# Serial.net
KiCad netlist of a schematic drawn in Altium Designer
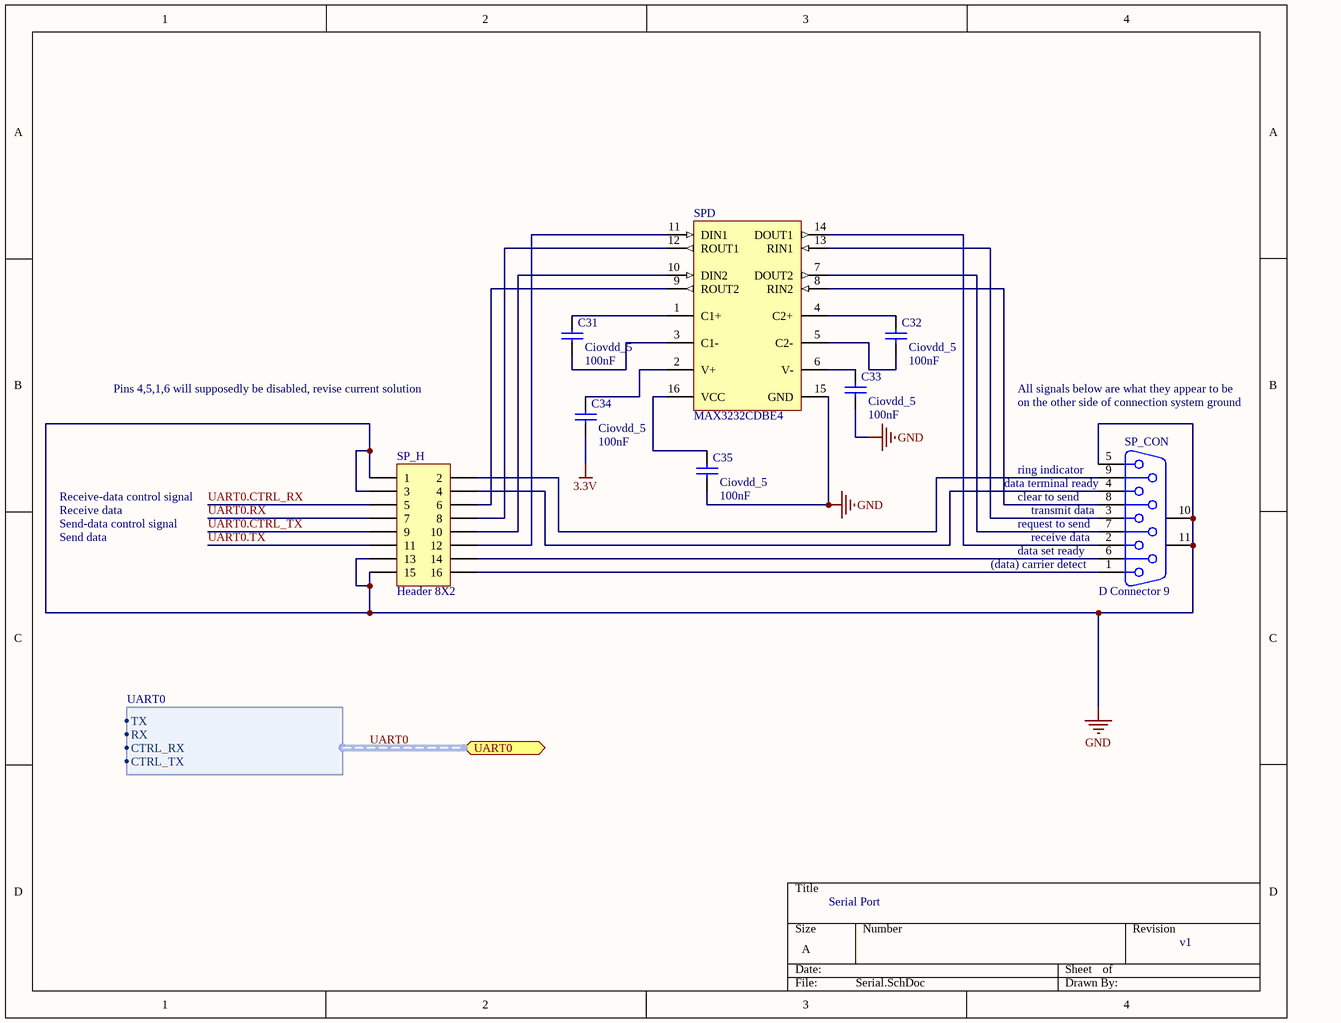
[diagram p0: Serial.SchDoc]

(export (version "E")
  (design (tool "Eeschema 10.0.6"))
  (components
    (comp (ref "C31")
      (value "Ciovdd_5")
      (footprint "C1206")
      (description "Capacitor (Semiconductor SIM Model)")
      (fields
        (field (name "ALTIUM_VALUE") "100nF")
        (field (name "MANUFACTURER") "AVX")
        (field (name "MANUFACTURER PART NUMBER") "02016D104KAT2A")
        (field (name "PUBLISHER") "Altium Limited")
      )
      (libsource (lib "Miscellaneous Devices") (part "Cap Semi"))
    )
    (comp (ref "C32")
      (value "Ciovdd_5")
      (footprint "C1206")
      (description "Capacitor (Semiconductor SIM Model)")
      (fields
        (field (name "ALTIUM_VALUE") "100nF")
        (field (name "MANUFACTURER") "AVX")
        (field (name "MANUFACTURER PART NUMBER") "02016D104KAT2A")
        (field (name "PUBLISHER") "Altium Limited")
      )
      (libsource (lib "Miscellaneous Devices") (part "Cap Semi"))
    )
    (comp (ref "C33")
      (value "Ciovdd_5")
      (footprint "C1206")
      (description "Capacitor (Semiconductor SIM Model)")
      (fields
        (field (name "ALTIUM_VALUE") "100nF")
        (field (name "MANUFACTURER") "AVX")
        (field (name "MANUFACTURER PART NUMBER") "02016D104KAT2A")
        (field (name "PUBLISHER") "Altium Limited")
      )
      (libsource (lib "Miscellaneous Devices") (part "Cap Semi"))
    )
    (comp (ref "C34")
      (value "Ciovdd_5")
      (footprint "C1206")
      (description "Capacitor (Semiconductor SIM Model)")
      (fields
        (field (name "ALTIUM_VALUE") "100nF")
        (field (name "MANUFACTURER") "AVX")
        (field (name "MANUFACTURER PART NUMBER") "02016D104KAT2A")
        (field (name "PUBLISHER") "Altium Limited")
      )
      (libsource (lib "Miscellaneous Devices") (part "Cap Semi"))
    )
    (comp (ref "C35")
      (value "Ciovdd_5")
      (footprint "C1206")
      (description "Capacitor (Semiconductor SIM Model)")
      (fields
        (field (name "ALTIUM_VALUE") "100nF")
        (field (name "MANUFACTURER") "AVX")
        (field (name "MANUFACTURER PART NUMBER") "02016D104KAT2A")
        (field (name "PUBLISHER") "Altium Limited")
      )
      (libsource (lib "Miscellaneous Devices") (part "Cap Semi"))
    )
    (comp (ref "SPD")
      (value "MAX3232CDBE4")
      (footprint "TI-DB16_L")
      (libsource (lib "Altium Content Vault") (part "TI-MAX3232-SSOP_DB-16"))
    )
    (comp (ref "SP_CON")
      (value "D Connector 9")
      (footprint "DSUB1.385-2H9")
      (description "Receptacle Assembly, 9 Position, Right Angle")
      (fields (field (name "PUBLISHER") "Altium Limited"))
      (libsource (lib "Miscellaneous Connectors") (part "D Connector 9"))
    )
    (comp (ref "SP_H")
      (value "Header 8X2")
      (footprint "HDR2X8")
      (description "Header, 8-Pin, Dual row")
      (fields (field (name "PUBLISHER") "Altium Limited"))
      (libsource (lib "Miscellaneous Connectors") (part "Header 8X2"))
    )
  )
  (nets
    (net (code "2") (name "/UART0.CTRL_RX") (class "Default")
      (node (ref "SP_H") (pin "5") (pinfunction "5_5") (pintype "passive"))
    )
    (net (code "3") (name "/UART0.CTRL_TX") (class "Default")
      (node (ref "SP_H") (pin "9") (pinfunction "9_9") (pintype "passive"))
    )
    (net (code "4") (name "/UART0.RX") (class "Default")
      (node (ref "SP_H") (pin "7") (pinfunction "7_7") (pintype "passive"))
    )
    (net (code "5") (name "/UART0.TX") (class "Default")
      (node (ref "SP_H") (pin "11") (pinfunction "11_11") (pintype "passive"))
    )
    (net (code "7") (name "3.3V") (class "Default")
      (node (ref "C34") (pin "1") (pinfunction "1_1") (pintype "passive"))
    )
    (net (code "8") (name "GND") (class "Default")
      (node (ref "C33") (pin "1") (pinfunction "1_1") (pintype "passive"))
      (node (ref "C35") (pin "1") (pinfunction "1_1") (pintype "passive"))
      (node (ref "SPD") (pin "15") (pinfunction "GND_15") (pintype "power_in"))
      (node (ref "SP_CON") (pin "10") (pinfunction "MH1_10") (pintype "passive"))
      (node (ref "SP_CON") (pin "11") (pinfunction "MH2_11") (pintype "passive"))
      (node (ref "SP_CON") (pin "5") (pinfunction "5_5") (pintype "passive"))
      (node (ref "SP_H") (pin "1") (pinfunction "1_1") (pintype "passive"))
      (node (ref "SP_H") (pin "13") (pinfunction "13_13") (pintype "passive"))
      (node (ref "SP_H") (pin "15") (pinfunction "15_15") (pintype "passive"))
      (node (ref "SP_H") (pin "3") (pinfunction "3_3") (pintype "passive"))
    )
    (net (code "9") (name "Net-(SPD-C1+)") (class "Default")
      (node (ref "C31") (pin "2") (pinfunction "2_2") (pintype "passive"))
      (node (ref "SPD") (pin "1") (pinfunction "C1+_1") (pintype "passive"))
    )
    (net (code "10") (name "Net-(SPD-C1-)") (class "Default")
      (node (ref "C31") (pin "1") (pinfunction "1_1") (pintype "passive"))
      (node (ref "SPD") (pin "3") (pinfunction "C1-_3") (pintype "passive"))
    )
    (net (code "11") (name "Net-(SPD-C2+)") (class "Default")
      (node (ref "C32") (pin "2") (pinfunction "2_2") (pintype "passive"))
      (node (ref "SPD") (pin "4") (pinfunction "C2+_4") (pintype "passive"))
    )
    (net (code "12") (name "Net-(SPD-C2-)") (class "Default")
      (node (ref "C32") (pin "1") (pinfunction "1_1") (pintype "passive"))
      (node (ref "SPD") (pin "5") (pinfunction "C2-_5") (pintype "passive"))
    )
    (net (code "13") (name "Net-(SPD-DIN1)") (class "Default")
      (node (ref "SPD") (pin "11") (pinfunction "DIN1_11") (pintype "input"))
      (node (ref "SP_H") (pin "12") (pinfunction "12_12") (pintype "passive"))
    )
    (net (code "14") (name "Net-(SPD-DIN2)") (class "Default")
      (node (ref "SPD") (pin "10") (pinfunction "DIN2_10") (pintype "input"))
      (node (ref "SP_H") (pin "10") (pinfunction "10_10") (pintype "passive"))
    )
    (net (code "15") (name "Net-(SPD-DOUT1)") (class "Default")
      (node (ref "SPD") (pin "14") (pinfunction "DOUT1_14") (pintype "output"))
      (node (ref "SP_CON") (pin "2") (pinfunction "2_2") (pintype "passive"))
    )
    (net (code "16") (name "Net-(SPD-DOUT2)") (class "Default")
      (node (ref "SPD") (pin "7") (pinfunction "DOUT2_7") (pintype "output"))
      (node (ref "SP_CON") (pin "7") (pinfunction "7_7") (pintype "passive"))
    )
    (net (code "17") (name "Net-(SPD-RIN1)") (class "Default")
      (node (ref "SPD") (pin "13") (pinfunction "RIN1_13") (pintype "input"))
      (node (ref "SP_CON") (pin "3") (pinfunction "3_3") (pintype "passive"))
    )
    (net (code "18") (name "Net-(SPD-RIN2)") (class "Default")
      (node (ref "SPD") (pin "8") (pinfunction "RIN2_8") (pintype "input"))
      (node (ref "SP_CON") (pin "8") (pinfunction "8_8") (pintype "passive"))
    )
    (net (code "19") (name "Net-(SPD-ROUT1)") (class "Default")
      (node (ref "SPD") (pin "12") (pinfunction "ROUT1_12") (pintype "output"))
      (node (ref "SP_H") (pin "8") (pinfunction "8_8") (pintype "passive"))
    )
    (net (code "20") (name "Net-(SPD-ROUT2)") (class "Default")
      (node (ref "SPD") (pin "9") (pinfunction "ROUT2_9") (pintype "output"))
      (node (ref "SP_H") (pin "6") (pinfunction "6_6") (pintype "passive"))
    )
    (net (code "21") (name "Net-(SPD-V+)") (class "Default")
      (node (ref "C34") (pin "2") (pinfunction "2_2") (pintype "passive"))
      (node (ref "SPD") (pin "2") (pinfunction "V+_2") (pintype "power_in"))
    )
    (net (code "22") (name "Net-(SPD-V-)") (class "Default")
      (node (ref "C33") (pin "2") (pinfunction "2_2") (pintype "passive"))
      (node (ref "SPD") (pin "6") (pinfunction "V-_6") (pintype "power_in"))
    )
    (net (code "23") (name "Net-(SPD-VCC)") (class "Default")
      (node (ref "C35") (pin "2") (pinfunction "2_2") (pintype "passive"))
      (node (ref "SPD") (pin "16") (pinfunction "VCC_16") (pintype "power_in"))
    )
    (net (code "24") (name "Net-(SP_CON-Pad1)") (class "Default")
      (node (ref "SP_CON") (pin "1") (pinfunction "1_1") (pintype "passive"))
      (node (ref "SP_H") (pin "16") (pinfunction "16_16") (pintype "passive"))
    )
    (net (code "25") (name "Net-(SP_CON-Pad4)") (class "Default")
      (node (ref "SP_CON") (pin "4") (pinfunction "4_4") (pintype "passive"))
      (node (ref "SP_H") (pin "4") (pinfunction "4_4") (pintype "passive"))
    )
    (net (code "26") (name "Net-(SP_CON-Pad6)") (class "Default")
      (node (ref "SP_CON") (pin "6") (pinfunction "6_6") (pintype "passive"))
      (node (ref "SP_H") (pin "14") (pinfunction "14_14") (pintype "passive"))
    )
    (net (code "27") (name "Net-(SP_CON-Pad9)") (class "Default")
      (node (ref "SP_CON") (pin "9") (pinfunction "9_9") (pintype "passive"))
      (node (ref "SP_H") (pin "2") (pinfunction "2_2") (pintype "passive"))
    )
  )
)
